# stepper-v1.net
KiCad netlist of a schematic drawn in EAGLE
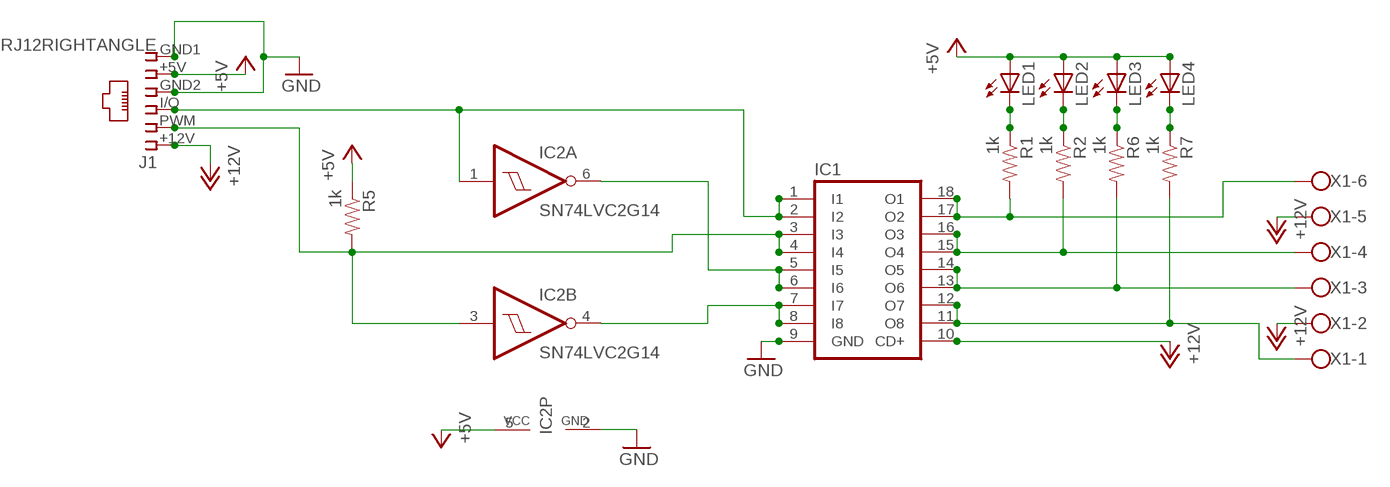
[diagram p0: schematic, sheet 1]

(export (version "E")
  (design (tool "Eeschema 10.0.6"))
  (components
    (comp (ref "IC1")
      (value "ULN2803A")
      (footprint "eagle-import:SO18W")
      (libsource (lib "eagle-import") (part "ULN2803A"))
    )
    (comp (ref "IC2")
      (value "SN74LVC2G14")
      (footprint "eagle-import:SOT23-6")
      (libsource (lib "eagle-import") (part "SN74LVC2G14"))
    )
    (comp (ref "J1")
      (value "RJ12RIGHTANGLE")
      (footprint "eagle-import:RJ12-RIGHTANGLE")
      (libsource (lib "eagle-import") (part "RJ12RIGHTANGLE"))
    )
    (comp (ref "LED1")
      (value "LED3MM")
      (footprint "eagle-import:LED3MM")
      (libsource (lib "eagle-import") (part "LED3MM"))
    )
    (comp (ref "LED2")
      (value "LED3MM")
      (footprint "eagle-import:LED3MM")
      (libsource (lib "eagle-import") (part "LED3MM"))
    )
    (comp (ref "LED3")
      (value "LED3MM")
      (footprint "eagle-import:LED3MM")
      (libsource (lib "eagle-import") (part "LED3MM"))
    )
    (comp (ref "LED4")
      (value "LED3MM")
      (footprint "eagle-import:LED3MM")
      (libsource (lib "eagle-import") (part "LED3MM"))
    )
    (comp (ref "R1")
      (value "1k")
      (footprint "eagle-import:1206")
      (libsource (lib "eagle-import") (part "RESISTOR1206"))
    )
    (comp (ref "R2")
      (value "1k")
      (footprint "eagle-import:1206")
      (libsource (lib "eagle-import") (part "RESISTOR1206"))
    )
    (comp (ref "R5")
      (value "1k")
      (footprint "eagle-import:1206")
      (libsource (lib "eagle-import") (part "RESISTOR1206"))
    )
    (comp (ref "R6")
      (value "1k")
      (footprint "eagle-import:1206")
      (libsource (lib "eagle-import") (part "RESISTOR1206"))
    )
    (comp (ref "R7")
      (value "1k")
      (footprint "eagle-import:1206")
      (libsource (lib "eagle-import") (part "RESISTOR1206"))
    )
    (comp (ref "X1")
      (value "W237-6")
      (footprint "eagle-import:W237-6")
      (libsource (lib "eagle-import") (part "W237-6"))
    )
  )
  (nets
    (net (code "1") (name "+5V") (class "Default")
      (node (ref "IC2") (pin "5") (pinfunction "VCC_5") (pintype "power_in"))
      (node (ref "J1") (pin "+5V") (pinfunction "5_+5V") (pintype "power_in"))
      (node (ref "LED1") (pin "A") (pinfunction "A_A") (pintype "passive"))
      (node (ref "LED2") (pin "A") (pinfunction "A_A") (pintype "passive"))
      (node (ref "LED3") (pin "A") (pinfunction "A_A") (pintype "passive"))
      (node (ref "LED4") (pin "A") (pinfunction "A_A") (pintype "passive"))
      (node (ref "R5") (pin "1") (pinfunction "1_1") (pintype "passive"))
    )
    (net (code "2") (name "+12V") (class "Default")
      (node (ref "IC1") (pin "10") (pinfunction "CD+_10") (pintype "passive"))
      (node (ref "J1") (pin "+12V") (pinfunction "1_+12V") (pintype "power_in"))
      (node (ref "X1") (pin "2") (pinfunction "KL_2") (pintype "passive"))
      (node (ref "X1") (pin "5") (pinfunction "KL_5") (pintype "passive"))
    )
    (net (code "3") (name "GND") (class "Default")
      (node (ref "IC1") (pin "9") (pinfunction "GND_9") (pintype "power_in"))
      (node (ref "IC2") (pin "2") (pinfunction "GND_2") (pintype "power_in"))
      (node (ref "J1") (pin "GND1") (pinfunction "6_GND1") (pintype "power_in"))
      (node (ref "J1") (pin "GND2") (pinfunction "4_GND2") (pintype "power_in"))
    )
    (net (code "4") (name "Net-(IC1-I1)") (class "Default")
      (node (ref "IC1") (pin "1") (pinfunction "I1_1") (pintype "input"))
      (node (ref "IC1") (pin "2") (pinfunction "I2_2") (pintype "input"))
      (node (ref "IC2") (pin "1") (pinfunction "I_1") (pintype "input"))
      (node (ref "J1") (pin "I/O") (pinfunction "3_I/O") (pintype "bidirectional"))
    )
    (net (code "5") (name "Net-(IC1-I3)") (class "Default")
      (node (ref "IC1") (pin "3") (pinfunction "I3_3") (pintype "input"))
      (node (ref "IC1") (pin "4") (pinfunction "I4_4") (pintype "input"))
      (node (ref "IC2") (pin "3") (pinfunction "I_3") (pintype "input"))
      (node (ref "J1") (pin "PWM") (pinfunction "2_PWM") (pintype "bidirectional"))
      (node (ref "R5") (pin "2") (pinfunction "2_2") (pintype "passive"))
    )
    (net (code "6") (name "Net-(IC1-I5)") (class "Default")
      (node (ref "IC1") (pin "5") (pinfunction "I5_5") (pintype "input"))
      (node (ref "IC1") (pin "6") (pinfunction "I6_6") (pintype "input"))
      (node (ref "IC2") (pin "6") (pinfunction "O_6") (pintype "output"))
    )
    (net (code "7") (name "Net-(IC1-I7)") (class "Default")
      (node (ref "IC1") (pin "7") (pinfunction "I7_7") (pintype "input"))
      (node (ref "IC1") (pin "8") (pinfunction "I8_8") (pintype "input"))
      (node (ref "IC2") (pin "4") (pinfunction "O_4") (pintype "output"))
    )
    (net (code "8") (name "Net-(IC1-O1)") (class "Default")
      (node (ref "IC1") (pin "17") (pinfunction "O2_17") (pintype "open_collector"))
      (node (ref "IC1") (pin "18") (pinfunction "O1_18") (pintype "open_collector"))
      (node (ref "R1") (pin "2") (pinfunction "2_2") (pintype "passive"))
      (node (ref "X1") (pin "6") (pinfunction "KL_6") (pintype "passive"))
    )
    (net (code "9") (name "Net-(IC1-O3)") (class "Default")
      (node (ref "IC1") (pin "15") (pinfunction "O4_15") (pintype "open_collector"))
      (node (ref "IC1") (pin "16") (pinfunction "O3_16") (pintype "open_collector"))
      (node (ref "R2") (pin "2") (pinfunction "2_2") (pintype "passive"))
      (node (ref "X1") (pin "4") (pinfunction "KL_4") (pintype "passive"))
    )
    (net (code "10") (name "Net-(IC1-O5)") (class "Default")
      (node (ref "IC1") (pin "13") (pinfunction "O6_13") (pintype "open_collector"))
      (node (ref "IC1") (pin "14") (pinfunction "O5_14") (pintype "open_collector"))
      (node (ref "R6") (pin "2") (pinfunction "2_2") (pintype "passive"))
      (node (ref "X1") (pin "3") (pinfunction "KL_3") (pintype "passive"))
    )
    (net (code "11") (name "Net-(IC1-O7)") (class "Default")
      (node (ref "IC1") (pin "11") (pinfunction "O8_11") (pintype "open_collector"))
      (node (ref "IC1") (pin "12") (pinfunction "O7_12") (pintype "open_collector"))
      (node (ref "R7") (pin "2") (pinfunction "2_2") (pintype "passive"))
      (node (ref "X1") (pin "1") (pinfunction "KL_1") (pintype "passive"))
    )
    (net (code "12") (name "Net-(LED1-C)") (class "Default")
      (node (ref "LED1") (pin "K") (pinfunction "C_K") (pintype "passive"))
      (node (ref "R1") (pin "1") (pinfunction "1_1") (pintype "passive"))
    )
    (net (code "13") (name "Net-(LED2-C)") (class "Default")
      (node (ref "LED2") (pin "K") (pinfunction "C_K") (pintype "passive"))
      (node (ref "R2") (pin "1") (pinfunction "1_1") (pintype "passive"))
    )
    (net (code "14") (name "Net-(LED3-C)") (class "Default")
      (node (ref "LED3") (pin "K") (pinfunction "C_K") (pintype "passive"))
      (node (ref "R6") (pin "1") (pinfunction "1_1") (pintype "passive"))
    )
    (net (code "15") (name "Net-(LED4-C)") (class "Default")
      (node (ref "LED4") (pin "K") (pinfunction "C_K") (pintype "passive"))
      (node (ref "R7") (pin "1") (pinfunction "1_1") (pintype "passive"))
    )
  )
)
